# SCH_ArgonLockModuleV2_2022-05-29.net
KiCad netlist of a schematic drawn in EasyEDA
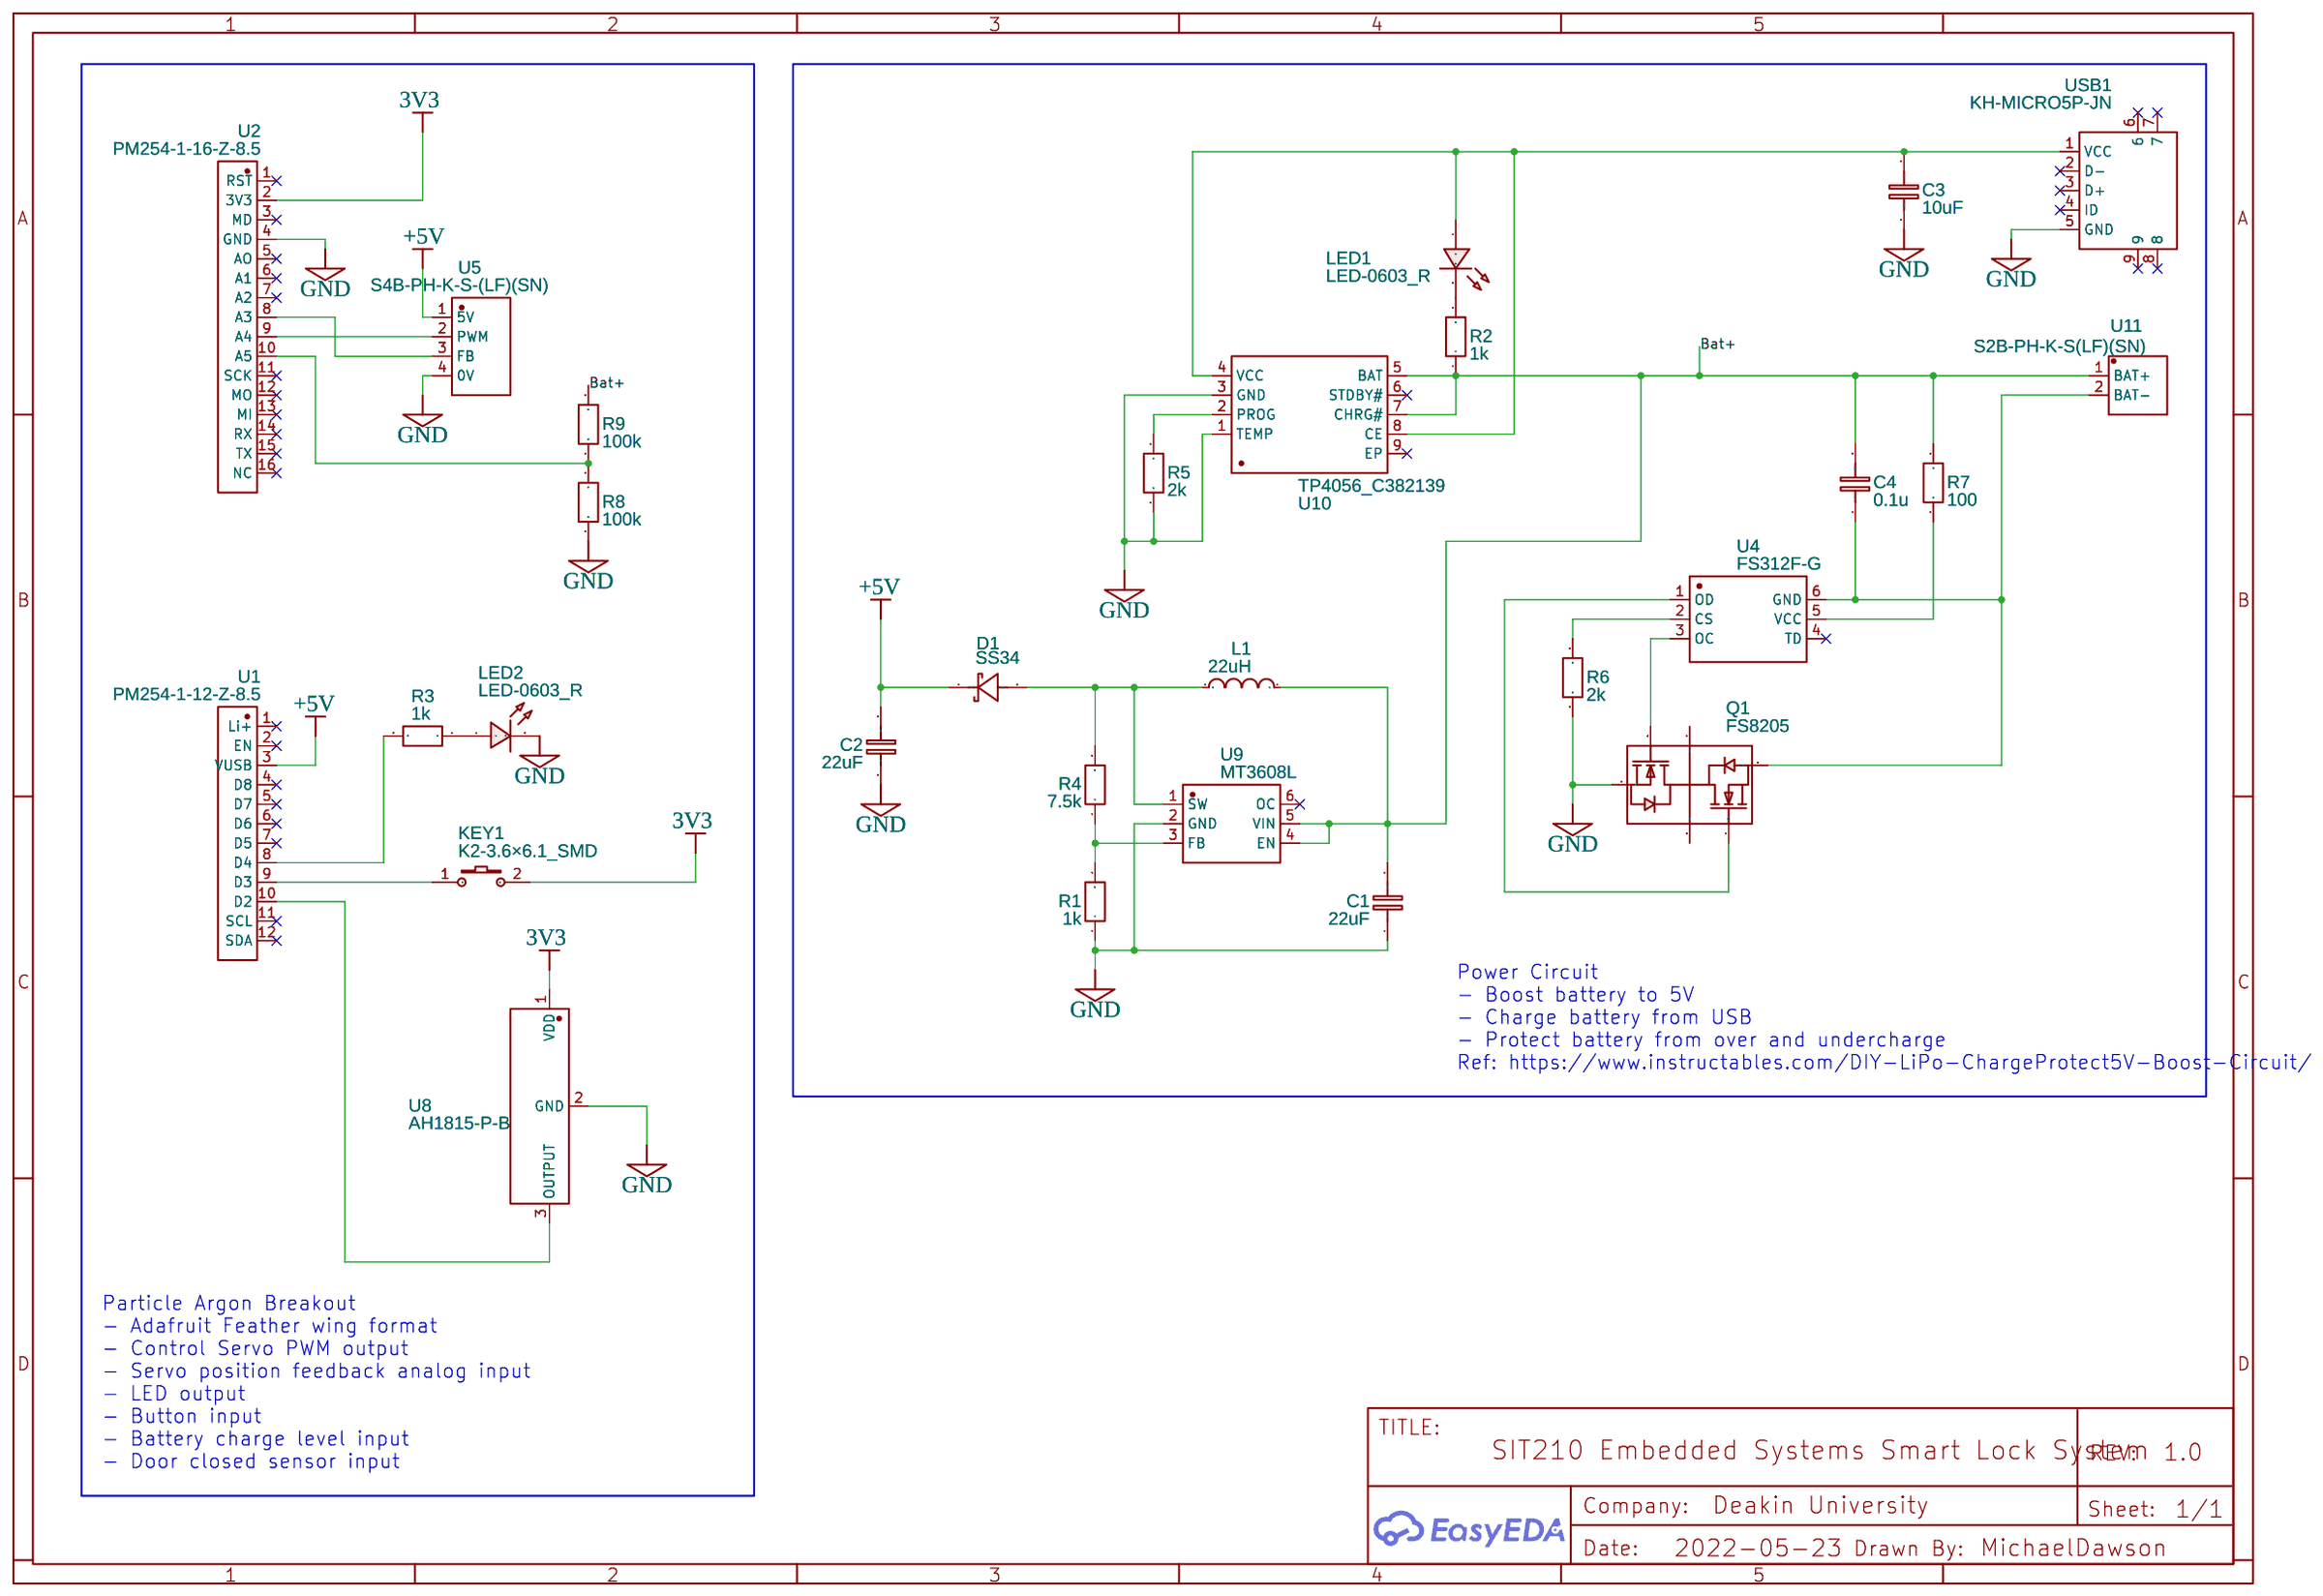
[diagram p0: schematic sheet]

(export (version "E")
  (design (tool "Eeschema 10.0.6"))
  (components
    (comp (ref "C1") (value "22uF") (libsource (lib "") (part "C_0603_EU_1")))
    (comp (ref "C2") (value "22uF") (libsource (lib "") (part "C_0603_EU_2")))
    (comp (ref "C3") (value "10uF") (libsource (lib "") (part "C_0603_EU")))
    (comp (ref "C4") (value "0.1u") (libsource (lib "") (part "C_0603_EU")))
    (comp (ref "D1")
      (value "SS34")
      (fields (field (name "BOM_Supplier Part") "C908680"))
      (libsource (lib "") (part "SS34_C908680"))
    )
    (comp (ref "KEY1")
      (value "K2-3.6×6.1_SMD")
      (fields
        (field (name "BOM_Manufacturer Part") "K2-1107ST-A4SW-06")
        (field (name "BOM_Supplier Part") "C118141")
      )
      (libsource (lib "") (part "K2-3.6×6.1_SMD"))
    )
    (comp (ref "L1")
      (value "22uH")
      (fields
        (field (name "BOM_Manufacturer Part") "MAPM1040F-220M-LF")
        (field (name "BOM_Supplier Part") "C280934")
      )
      (libsource (lib "") (part "MAPM1040F-220M-LF"))
    )
    (comp (ref "LED1")
      (value "LED-0603_R")
      (fields
        (field (name "BOM_Manufacturer Part") "19-217/R6C-AL1M2VY/3T")
        (field (name "BOM_Supplier Part") "C72044")
      )
      (libsource (lib "") (part "LED-0603_R"))
    )
    (comp (ref "LED2")
      (value "LED-0603_R")
      (fields
        (field (name "BOM_Manufacturer Part") "19-217/R6C-AL1M2VY/3T")
        (field (name "BOM_Supplier Part") "C72044")
      )
      (libsource (lib "") (part "LED-0603_R_1"))
    )
    (comp (ref "Q1")
      (value "FS8205")
      (fields (field (name "BOM_Supplier Part") "C32254"))
      (libsource (lib "") (part "FS8205"))
    )
    (comp (ref "R1") (value "1k") (libsource (lib "") (part "R_0603_EU")))
    (comp (ref "R2") (value "1k") (libsource (lib "") (part "R_0603_EU")))
    (comp (ref "R3") (value "1k") (libsource (lib "") (part "R_0603_EU_2")))
    (comp (ref "R4") (value "7.5k") (libsource (lib "") (part "R_0603_EU")))
    (comp (ref "R5") (value "2k") (libsource (lib "") (part "R_0603_EU_1")))
    (comp (ref "R6") (value "2k") (libsource (lib "") (part "R_0603_EU")))
    (comp (ref "R7") (value "100") (libsource (lib "") (part "R_0603_EU")))
    (comp (ref "R8") (value "100k") (libsource (lib "") (part "R_0603_EU")))
    (comp (ref "R9") (value "100k") (libsource (lib "") (part "R_0603_EU")))
    (comp (ref "U1")
      (value "PM254-1-12-Z-8.5")
      (fields (field (name "BOM_Supplier Part") "C2897375"))
      (libsource (lib "") (part "PM254-1-12-Z-8.5"))
    )
    (comp (ref "U2")
      (value "PM254-1-16-Z-8.5")
      (fields (field (name "BOM_Supplier Part") "C2897379"))
      (libsource (lib "") (part "PM254-1-16-Z-8.5"))
    )
    (comp (ref "U4")
      (value "FS312F-G")
      (fields (field (name "BOM_Supplier Part") "C82736"))
      (libsource (lib "") (part "FS312F-G"))
    )
    (comp (ref "U5")
      (value "S4B-PH-K-S-(LF)(SN)")
      (fields (field (name "BOM_Supplier Part") "C157926"))
      (libsource (lib "") (part "S4B-PH-K-S-(LF)(SN)"))
    )
    (comp (ref "U8")
      (value "AH1815-P-B")
      (fields (field (name "BOM_Supplier Part") "C151373"))
      (libsource (lib "") (part "AH1815-P-B"))
    )
    (comp (ref "U9")
      (value "MT3608L")
      (fields (field (name "BOM_Supplier Part") "C2932326"))
      (libsource (lib "") (part "MT3608L"))
    )
    (comp (ref "U10")
      (value "TP4056_C382139")
      (fields (field (name "BOM_Manufacturer Part") "TP4056") (field (name "BOM_Supplier Part") "C382139"))
      (libsource (lib "") (part "TP4056_C382139"))
    )
    (comp (ref "U11")
      (value "S2B-PH-K-S(LF)(SN)")
      (fields (field (name "BOM_Supplier Part") "C173752"))
      (libsource (lib "") (part "S2B-PH-K-S(LF)(SN)"))
    )
    (comp (ref "USB1")
      (value "KH-MICRO5P-JN")
      (fields (field (name "BOM_Supplier Part") "C962222"))
      (libsource (lib "") (part "KH-MICRO5P-JN"))
    )
  )
  (nets
    (net (code "1") (name "+5V") (class "Default")
      (node (ref "C2") (pin "2") (pinfunction "2_2") (pintype "unspecified"))
      (node (ref "D1") (pin "1") (pinfunction "C_1") (pintype "unspecified"))
      (node (ref "U1") (pin "3") (pinfunction "VUSB_3") (pintype "unspecified"))
      (node (ref "U5") (pin "1") (pinfunction "5V_1") (pintype "unspecified"))
    )
    (net (code "2") (name "/Bat+") (class "Default")
      (node (ref "C1") (pin "2") (pinfunction "2_2") (pintype "unspecified"))
      (node (ref "C4") (pin "2") (pinfunction "2_2") (pintype "unspecified"))
      (node (ref "L1") (pin "1") (pinfunction "1_1") (pintype "unspecified"))
      (node (ref "R2") (pin "1") (pinfunction "1_1") (pintype "unspecified"))
      (node (ref "R7") (pin "2") (pinfunction "2_2") (pintype "unspecified"))
      (node (ref "R9") (pin "2") (pinfunction "2_2") (pintype "unspecified"))
      (node (ref "U10") (pin "5") (pinfunction "BAT_5") (pintype "unspecified"))
      (node (ref "U10") (pin "7") (pinfunction "CHRG#_7") (pintype "unspecified"))
      (node (ref "U11") (pin "1") (pinfunction "BAT+_1") (pintype "unspecified"))
      (node (ref "U9") (pin "4") (pinfunction "EN_4") (pintype "unspecified"))
      (node (ref "U9") (pin "5") (pinfunction "VIN_5") (pintype "unspecified"))
    )
    (net (code "3") (name "3V3") (class "Default")
      (node (ref "KEY1") (pin "2") (pinfunction "2_2") (pintype "unspecified"))
      (node (ref "U2") (pin "2") (pinfunction "3V3_2") (pintype "unspecified"))
      (node (ref "U8") (pin "1") (pinfunction "VDD_1") (pintype "unspecified"))
    )
    (net (code "4") (name "GND") (class "Default")
      (node (ref "C1") (pin "1") (pinfunction "1_1") (pintype "unspecified"))
      (node (ref "C2") (pin "1") (pinfunction "1_1") (pintype "unspecified"))
      (node (ref "C3") (pin "1") (pinfunction "1_1") (pintype "unspecified"))
      (node (ref "LED2") (pin "2") (pinfunction "2_2") (pintype "unspecified"))
      (node (ref "Q1") (pin "1") (pinfunction "S1_1") (pintype "unspecified"))
      (node (ref "R1") (pin "1") (pinfunction "1_1") (pintype "unspecified"))
      (node (ref "R5") (pin "2") (pinfunction "2_2") (pintype "unspecified"))
      (node (ref "R6") (pin "1") (pinfunction "1_1") (pintype "unspecified"))
      (node (ref "R8") (pin "1") (pinfunction "1_1") (pintype "unspecified"))
      (node (ref "U10") (pin "1") (pinfunction "TEMP_1") (pintype "unspecified"))
      (node (ref "U10") (pin "3") (pinfunction "GND_3") (pintype "unspecified"))
      (node (ref "U2") (pin "4") (pinfunction "GND_4") (pintype "unspecified"))
      (node (ref "U5") (pin "4") (pinfunction "0V_4") (pintype "unspecified"))
      (node (ref "U8") (pin "2") (pinfunction "GND_2") (pintype "unspecified"))
      (node (ref "U9") (pin "2") (pinfunction "GND_2") (pintype "unspecified"))
      (node (ref "USB1") (pin "5") (pinfunction "GND_5") (pintype "input"))
    )
    (net (code "5") (name "Net-(D1-A)") (class "Default")
      (node (ref "D1") (pin "2") (pinfunction "A_2") (pintype "unspecified"))
      (node (ref "L1") (pin "2") (pinfunction "2_2") (pintype "unspecified"))
      (node (ref "R4") (pin "2") (pinfunction "2_2") (pintype "unspecified"))
      (node (ref "U9") (pin "1") (pinfunction "SW_1") (pintype "unspecified"))
    )
    (net (code "6") (name "Net-(LED1-Pad2)") (class "Default")
      (node (ref "LED1") (pin "2") (pinfunction "2_2") (pintype "unspecified"))
      (node (ref "R2") (pin "2") (pinfunction "2_2") (pintype "unspecified"))
    )
    (net (code "7") (name "Net-(LED2-Pad1)") (class "Default")
      (node (ref "LED2") (pin "1") (pinfunction "1_1") (pintype "unspecified"))
      (node (ref "R3") (pin "1") (pinfunction "1_1") (pintype "unspecified"))
    )
    (net (code "8") (name "Net-(Q1-G1)") (class "Default")
      (node (ref "Q1") (pin "6") (pinfunction "G1_6") (pintype "unspecified"))
      (node (ref "U4") (pin "3") (pinfunction "OC_3") (pintype "unspecified"))
    )
    (net (code "9") (name "Net-(Q1-G2)") (class "Default")
      (node (ref "Q1") (pin "4") (pinfunction "G2_4") (pintype "unspecified"))
      (node (ref "U4") (pin "1") (pinfunction "OD_1") (pintype "unspecified"))
    )
    (net (code "10") (name "Net-(Q1-S2)") (class "Default")
      (node (ref "C4") (pin "1") (pinfunction "1_1") (pintype "unspecified"))
      (node (ref "Q1") (pin "3") (pinfunction "S2_3") (pintype "unspecified"))
      (node (ref "U11") (pin "2") (pinfunction "BAT-_2") (pintype "unspecified"))
      (node (ref "U4") (pin "6") (pinfunction "GND_6") (pintype "unspecified"))
    )
    (net (code "11") (name "Net-(U1-D2)") (class "Default")
      (node (ref "U1") (pin "10") (pinfunction "D2_10") (pintype "unspecified"))
      (node (ref "U8") (pin "3") (pinfunction "OUTPUT_3") (pintype "unspecified"))
    )
    (net (code "12") (name "Net-(U1-D3)") (class "Default")
      (node (ref "KEY1") (pin "1") (pinfunction "1_1") (pintype "unspecified"))
      (node (ref "U1") (pin "9") (pinfunction "D3_9") (pintype "unspecified"))
    )
    (net (code "13") (name "Net-(U1-D4)") (class "Default")
      (node (ref "R3") (pin "2") (pinfunction "2_2") (pintype "unspecified"))
      (node (ref "U1") (pin "8") (pinfunction "D4_8") (pintype "unspecified"))
    )
    (net (code "14") (name "Net-(U2-A3)") (class "Default")
      (node (ref "U2") (pin "8") (pinfunction "A3_8") (pintype "unspecified"))
      (node (ref "U5") (pin "3") (pinfunction "FB_3") (pintype "unspecified"))
    )
    (net (code "15") (name "Net-(U2-A4)") (class "Default")
      (node (ref "U2") (pin "9") (pinfunction "A4_9") (pintype "unspecified"))
      (node (ref "U5") (pin "2") (pinfunction "PWM_2") (pintype "unspecified"))
    )
    (net (code "16") (name "Net-(U2-A5)") (class "Default")
      (node (ref "R8") (pin "2") (pinfunction "2_2") (pintype "unspecified"))
      (node (ref "R9") (pin "1") (pinfunction "1_1") (pintype "unspecified"))
      (node (ref "U2") (pin "10") (pinfunction "A5_10") (pintype "unspecified"))
    )
    (net (code "17") (name "Net-(U4-CS)") (class "Default")
      (node (ref "R6") (pin "2") (pinfunction "2_2") (pintype "unspecified"))
      (node (ref "U4") (pin "2") (pinfunction "CS_2") (pintype "unspecified"))
    )
    (net (code "18") (name "Net-(U4-VCC)") (class "Default")
      (node (ref "R7") (pin "1") (pinfunction "1_1") (pintype "unspecified"))
      (node (ref "U4") (pin "5") (pinfunction "VCC_5") (pintype "unspecified"))
    )
    (net (code "19") (name "Net-(U9-FB)") (class "Default")
      (node (ref "R1") (pin "2") (pinfunction "2_2") (pintype "unspecified"))
      (node (ref "R4") (pin "1") (pinfunction "1_1") (pintype "unspecified"))
      (node (ref "U9") (pin "3") (pinfunction "FB_3") (pintype "unspecified"))
    )
    (net (code "20") (name "Net-(U10-CE)") (class "Default")
      (node (ref "C3") (pin "2") (pinfunction "2_2") (pintype "unspecified"))
      (node (ref "LED1") (pin "1") (pinfunction "1_1") (pintype "unspecified"))
      (node (ref "U10") (pin "4") (pinfunction "VCC_4") (pintype "unspecified"))
      (node (ref "U10") (pin "8") (pinfunction "CE_8") (pintype "unspecified"))
      (node (ref "USB1") (pin "1") (pinfunction "VCC_1") (pintype "input"))
    )
    (net (code "21") (name "Net-(U10-PROG)") (class "Default")
      (node (ref "R5") (pin "1") (pinfunction "1_1") (pintype "unspecified"))
      (node (ref "U10") (pin "2") (pinfunction "PROG_2") (pintype "unspecified"))
    )
    (net (code "22") (name "unconnected-(Q1-D12-Pad2)") (class "Default")
      (node (ref "Q1") (pin "2") (pinfunction "D12_2") (pintype "unspecified"))
    )
    (net (code "23") (name "unconnected-(Q1-D12-Pad5)") (class "Default")
      (node (ref "Q1") (pin "5") (pinfunction "D12_5") (pintype "unspecified"))
    )
    (net (code "24") (name "unconnected-(U1-D5-Pad7)") (class "Default")
      (node (ref "U1") (pin "7") (pinfunction "D5_7") (pintype "unspecified+no_connect"))
    )
    (net (code "25") (name "unconnected-(U1-D6-Pad6)") (class "Default")
      (node (ref "U1") (pin "6") (pinfunction "D6_6") (pintype "unspecified+no_connect"))
    )
    (net (code "26") (name "unconnected-(U1-D7-Pad5)") (class "Default")
      (node (ref "U1") (pin "5") (pinfunction "D7_5") (pintype "unspecified+no_connect"))
    )
    (net (code "27") (name "unconnected-(U1-D8-Pad4)") (class "Default")
      (node (ref "U1") (pin "4") (pinfunction "D8_4") (pintype "unspecified+no_connect"))
    )
    (net (code "28") (name "unconnected-(U1-EN-Pad2)") (class "Default")
      (node (ref "U1") (pin "2") (pinfunction "EN_2") (pintype "unspecified+no_connect"))
    )
    (net (code "29") (name "unconnected-(U1-Li+-Pad1)") (class "Default")
      (node (ref "U1") (pin "1") (pinfunction "Li+_1") (pintype "unspecified+no_connect"))
    )
    (net (code "30") (name "unconnected-(U1-SCL-Pad11)") (class "Default")
      (node (ref "U1") (pin "11") (pinfunction "SCL_11") (pintype "unspecified+no_connect"))
    )
    (net (code "31") (name "unconnected-(U1-SDA-Pad12)") (class "Default")
      (node (ref "U1") (pin "12") (pinfunction "SDA_12") (pintype "unspecified+no_connect"))
    )
    (net (code "32") (name "unconnected-(U2-A1-Pad6)") (class "Default")
      (node (ref "U2") (pin "6") (pinfunction "A1_6") (pintype "unspecified+no_connect"))
    )
    (net (code "33") (name "unconnected-(U2-A2-Pad7)") (class "Default")
      (node (ref "U2") (pin "7") (pinfunction "A2_7") (pintype "unspecified+no_connect"))
    )
    (net (code "34") (name "unconnected-(U2-AO-Pad5)") (class "Default")
      (node (ref "U2") (pin "5") (pinfunction "AO_5") (pintype "unspecified+no_connect"))
    )
    (net (code "35") (name "unconnected-(U2-MD-Pad3)") (class "Default")
      (node (ref "U2") (pin "3") (pinfunction "MD_3") (pintype "unspecified+no_connect"))
    )
    (net (code "36") (name "unconnected-(U2-MI-Pad13)") (class "Default")
      (node (ref "U2") (pin "13") (pinfunction "MI_13") (pintype "unspecified+no_connect"))
    )
    (net (code "37") (name "unconnected-(U2-MO-Pad12)") (class "Default")
      (node (ref "U2") (pin "12") (pinfunction "MO_12") (pintype "unspecified+no_connect"))
    )
    (net (code "38") (name "unconnected-(U2-NC-Pad16)") (class "Default")
      (node (ref "U2") (pin "16") (pinfunction "NC_16") (pintype "unspecified+no_connect"))
    )
    (net (code "39") (name "unconnected-(U2-RST-Pad1)") (class "Default")
      (node (ref "U2") (pin "1") (pinfunction "RST_1") (pintype "unspecified+no_connect"))
    )
    (net (code "40") (name "unconnected-(U2-RX-Pad14)") (class "Default")
      (node (ref "U2") (pin "14") (pinfunction "RX_14") (pintype "unspecified+no_connect"))
    )
    (net (code "41") (name "unconnected-(U2-SCK-Pad11)") (class "Default")
      (node (ref "U2") (pin "11") (pinfunction "SCK_11") (pintype "unspecified+no_connect"))
    )
    (net (code "42") (name "unconnected-(U2-TX-Pad15)") (class "Default")
      (node (ref "U2") (pin "15") (pinfunction "TX_15") (pintype "unspecified+no_connect"))
    )
    (net (code "43") (name "unconnected-(U4-TD-Pad4)") (class "Default")
      (node (ref "U4") (pin "4") (pinfunction "TD_4") (pintype "unspecified+no_connect"))
    )
    (net (code "44") (name "unconnected-(U9-OC-Pad6)") (class "Default")
      (node (ref "U9") (pin "6") (pinfunction "OC_6") (pintype "unspecified+no_connect"))
    )
    (net (code "45") (name "unconnected-(U10-EP-Pad9)") (class "Default")
      (node (ref "U10") (pin "9") (pinfunction "EP_9") (pintype "unspecified+no_connect"))
    )
    (net (code "46") (name "unconnected-(U10-STDBY#-Pad6)") (class "Default")
      (node (ref "U10") (pin "6") (pinfunction "STDBY#_6") (pintype "unspecified+no_connect"))
    )
    (net (code "47") (name "unconnected-(USB1-D+-Pad3)") (class "Default")
      (node (ref "USB1") (pin "3") (pinfunction "D+_3") (pintype "input+no_connect"))
    )
    (net (code "48") (name "unconnected-(USB1-D--Pad2)") (class "Default")
      (node (ref "USB1") (pin "2") (pinfunction "D-_2") (pintype "input+no_connect"))
    )
    (net (code "49") (name "unconnected-(USB1-ID-Pad4)") (class "Default")
      (node (ref "USB1") (pin "4") (pinfunction "ID_4") (pintype "input+no_connect"))
    )
    (net (code "50") (name "unconnected-(USB1-Pad6)") (class "Default")
      (node (ref "USB1") (pin "6") (pinfunction "6_6") (pintype "unspecified+no_connect"))
    )
    (net (code "51") (name "unconnected-(USB1-Pad7)") (class "Default")
      (node (ref "USB1") (pin "7") (pinfunction "7_7") (pintype "unspecified+no_connect"))
    )
    (net (code "52") (name "unconnected-(USB1-Pad8)") (class "Default")
      (node (ref "USB1") (pin "8") (pinfunction "8_8") (pintype "unspecified+no_connect"))
    )
    (net (code "53") (name "unconnected-(USB1-Pad9)") (class "Default")
      (node (ref "USB1") (pin "9") (pinfunction "9_9") (pintype "unspecified+no_connect"))
    )
  )
)
